# STM32_microcontroller_IOs.net
KiCad netlist of a schematic drawn in Altium Designer
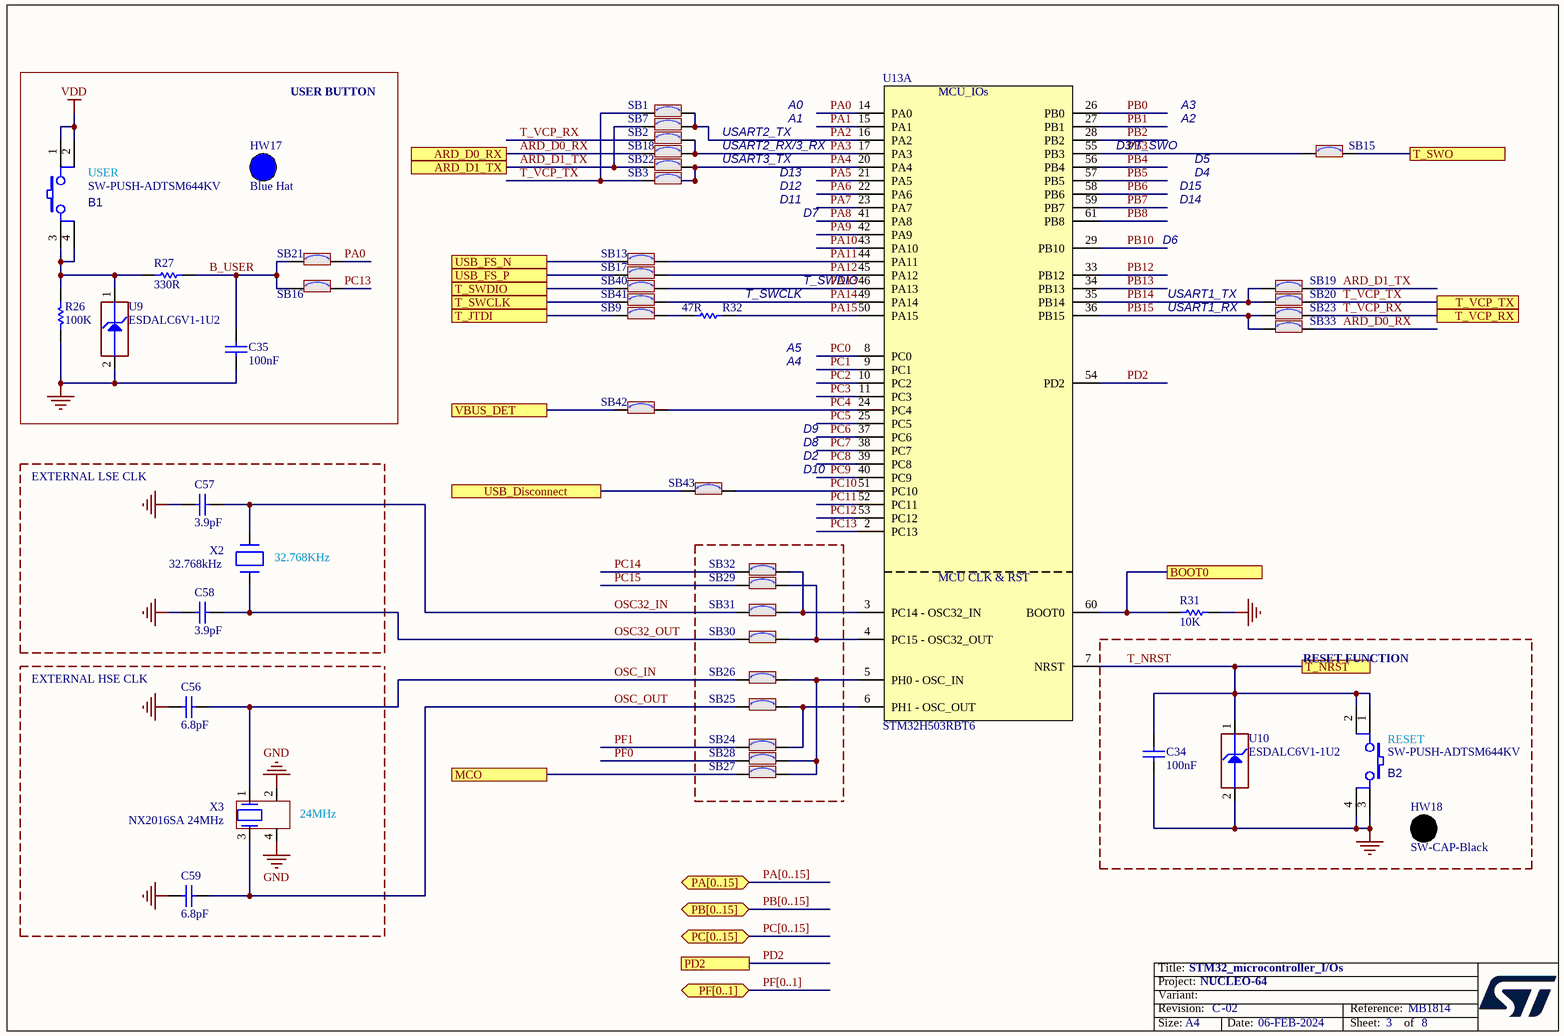
[diagram p0: STM32_microcontroller_IOs.SchDoc]

(export (version "E")
  (design (tool "Eeschema 10.0.6"))
  (components
    (comp (ref "B1")
      (value "SW-PUSH-ADTSM644KV")
      (footprint "SWI_APEM_ADTSM644KV_BLACK")
      (description "Push Button, SPST-NO, 0.05A, 12V SMT, T=7.30mm, changeable caps AKTSC62x")
      (fields (field (name "INTERNAL_PART_NUMBER") "MCD-02524") (field (name "MANUFACTURER") "APEM INC"))
      (libsource (lib "MCD_PARTS_database") (part "SW_PUSH_SMD"))
    )
    (comp (ref "B2")
      (value "SW-PUSH-ADTSM644KV")
      (footprint "SWI_APEM_ADTSM644KV_BLACK")
      (description "Push Button, SPST-NO, 0.05A, 12V SMT, T=7.30mm, changeable caps AKTSC62x")
      (fields (field (name "INTERNAL_PART_NUMBER") "MCD-02524") (field (name "MANUFACTURER") "APEM INC"))
      (libsource (lib "MCD_PARTS_database") (part "SW_PUSH_SMD"))
    )
    (comp (ref "C34")
      (value "100nF")
      (footprint "C0402")
      (description "Capacitor, MLCC, 100nF, 16V, X7R, +/-10%, 0402, T=0.5mm")
      (fields (field (name "INTERNAL_PART_NUMBER") "MCD-00006") (field (name "MANUFACTURER") "YAGEO"))
      (libsource (lib "MCD_PARTS_database") (part "Capacitor"))
    )
    (comp (ref "C35")
      (value "100nF")
      (footprint "C0402")
      (description "Capacitor, MLCC, 100nF, 16V, X7R, +/-10%, 0402, T=0.5mm")
      (fields (field (name "INTERNAL_PART_NUMBER") "MCD-00006") (field (name "MANUFACTURER") "YAGEO"))
      (libsource (lib "MCD_PARTS_database") (part "Capacitor"))
    )
    (comp (ref "C56")
      (value "6.8pF")
      (footprint "C0402")
      (description "Capacitor, MLCC, 6.8pF, 50V, NPO, +-0.25pF, 0402, T=0.5mm")
      (fields
        (field (name "INTERNAL_PART_NUMBER") "MCD-00674")
        (field (name "MANUFACTURER_PART_NUMBER") "CC0402CRNPO9BN6R8")
        (field (name "PROVIDED_BY") "SUBCO")
      )
      (libsource (lib "MCD_PARTS_database") (part "Capacitor"))
    )
    (comp (ref "C57")
      (value "3.9pF")
      (footprint "C0402")
      (description "Capacitor, MLCC, 3.9pF, 50V, NPO, +/-0.1pF, 0402, T=0.5mm")
      (fields (field (name "INTERNAL_PART_NUMBER") "MCD-01602") (field (name "MANUFACTURER") "YAGEO"))
      (libsource (lib "MCD_PARTS_database") (part "Capacitor"))
    )
    (comp (ref "C58")
      (value "3.9pF")
      (footprint "C0402")
      (description "Capacitor, MLCC, 3.9pF, 50V, NPO, +/-0.1pF, 0402, T=0.5mm")
      (fields (field (name "INTERNAL_PART_NUMBER") "MCD-01602") (field (name "MANUFACTURER") "YAGEO"))
      (libsource (lib "MCD_PARTS_database") (part "Capacitor"))
    )
    (comp (ref "C59")
      (value "6.8pF")
      (footprint "C0402")
      (description "Capacitor, MLCC, 6.8pF, 50V, NPO, +-0.25pF, 0402, T=0.5mm")
      (fields
        (field (name "INTERNAL_PART_NUMBER") "MCD-00674")
        (field (name "MANUFACTURER_PART_NUMBER") "CC0402CRNPO9BN6R8")
        (field (name "PROVIDED_BY") "SUBCO")
      )
      (libsource (lib "MCD_PARTS_database") (part "Capacitor"))
    )
    (comp (ref "HW17")
      (value "Blue Hat")
      (description "Switch hat, blue, For KTSC-62B")
      (fields (field (name "INTERNAL_PART_NUMBER") "MCD-02136") (field (name "MANUFACTURER") "APEM INC"))
      (libsource (lib "MCD_PARTS_database") (part "BUTTON_HAT_BLUE"))
    )
    (comp (ref "HW18")
      (value "SW-CAP-Black")
      (footprint "N/A")
      (description "Black round cap for ADTSM644KV")
      (fields (field (name "INTERNAL_PART_NUMBER") "MCD-02526") (field (name "MANUFACTURER") "APEM INC"))
      (libsource (lib "MCD_PARTS_database") (part "SW-CAP-Black"))
    )
    (comp (ref "R26")
      (value "100K")
      (footprint "R0603")
      (description "Resistor,100K,0603,1%,1/10W")
      (fields
        (field (name "INTERNAL_PART_NUMBER") "MCD-00223")
        (field (name "MANUFACTURER_PART_NUMBER") "RC0603FR-07100KL")
        (field (name "PROVIDED_BY") "Subcon")
      )
      (libsource (lib "MCD_PARTS_database") (part "Resistor"))
    )
    (comp (ref "R27")
      (value "330R")
      (footprint "R0603")
      (description "Resistor,330R,0603,1%,1/10W")
      (fields
        (field (name "INTERNAL_PART_NUMBER") "MCD-00197")
        (field (name "MANUFACTURER_PART_NUMBER") "RC0603FR-07330RL")
        (field (name "PROVIDED_BY") "Subcon")
      )
      (libsource (lib "MCD_PARTS_database") (part "Resistor"))
    )
    (comp (ref "R31")
      (value "10K")
      (footprint "R0603")
      (description "Resistor,10K,0603,1%,1/10W")
      (fields
        (field (name "INTERNAL_PART_NUMBER") "MCD-00220")
        (field (name "MANUFACTURER_PART_NUMBER") "RC0603FR-0710KL")
        (field (name "PROVIDED_BY") "Subcon")
      )
      (libsource (lib "MCD_PARTS_database") (part "Resistor"))
    )
    (comp (ref "R32")
      (value "47R")
      (footprint "R0402")
      (description "Resistor,47R,0402,1%,1/16W")
      (fields
        (field (name "INTERNAL_PART_NUMBER") "MCD-00481")
        (field (name "MANUFACTURER_PART_NUMBER") "RC0402FR-0747RL")
        (field (name "PROVIDED_BY") "SUBCO")
      )
      (libsource (lib "MCD_PARTS_database") (part "Resistor"))
    )
    (comp (ref "SB1")
      (value "~")
      (footprint "SOLDER-BRIDGE_R0603-0R")
      (description "Solder Bridge ON")
      (fields
        (field (name "INTERNAL_PART_NUMBER") "MCD-00071")
        (field (name "MANUFACTURER_PART_NUMBER") "RC0603JR-070RL")
        (field (name "PROVIDED_BY") "SUBCO")
      )
      (libsource (lib "") (part "SB_ON_1"))
    )
    (comp (ref "SB2")
      (value "~")
      (footprint "SOLDER-BRIDGE_R0603-0R")
      (description "Solder Bridge ON")
      (fields
        (field (name "INTERNAL_PART_NUMBER") "MCD-00071")
        (field (name "MANUFACTURER_PART_NUMBER") "RC0603JR-070RL")
        (field (name "PROVIDED_BY") "SUBCO")
      )
      (libsource (lib "") (part "SB_ON_1"))
    )
    (comp (ref "SB3")
      (value "~")
      (footprint "SOLDER-BRIDGE_R0603-0R")
      (description "Solder Bridge ON")
      (fields
        (field (name "INTERNAL_PART_NUMBER") "MCD-00071")
        (field (name "MANUFACTURER_PART_NUMBER") "RC0603JR-070RL")
        (field (name "PROVIDED_BY") "SUBCO")
      )
      (libsource (lib "") (part "SB_ON_1"))
    )
    (comp (ref "SB7")
      (value "~")
      (footprint "SOLDER-BRIDGE_R0603-0R")
      (description "Solder Bridge ON")
      (fields
        (field (name "INTERNAL_PART_NUMBER") "MCD-00071")
        (field (name "MANUFACTURER_PART_NUMBER") "RC0603JR-070RL")
        (field (name "PROVIDED_BY") "SUBCO")
      )
      (libsource (lib "") (part "SB_ON_1"))
    )
    (comp (ref "SB9")
      (value "~")
      (footprint "SOLDER-BRIDGE_R0603-0R")
      (description "Solder Bridge ON")
      (fields
        (field (name "INTERNAL_PART_NUMBER") "MCD-00071")
        (field (name "MANUFACTURER_PART_NUMBER") "RC0603JR-070RL")
        (field (name "PROVIDED_BY") "SUBCO")
      )
      (libsource (lib "MCD_PARTS_database") (part "SB_ON"))
    )
    (comp (ref "SB13")
      (value "~")
      (footprint "SOLDER-BRIDGE_R0603-0R")
      (description "Solder Bridge ON")
      (fields
        (field (name "INTERNAL_PART_NUMBER") "MCD-00071")
        (field (name "MANUFACTURER_PART_NUMBER") "RC0603JR-070RL")
        (field (name "PROVIDED_BY") "SUBCO")
      )
      (libsource (lib "MCD_PARTS_database") (part "SB_ON"))
    )
    (comp (ref "SB15")
      (value "~")
      (footprint "SOLDER-BRIDGE_R0603-0R")
      (description "Solder Bridge ON")
      (fields
        (field (name "INTERNAL_PART_NUMBER") "MCD-00071")
        (field (name "MANUFACTURER_PART_NUMBER") "RC0603JR-070RL")
        (field (name "PROVIDED_BY") "SUBCO")
      )
      (libsource (lib "MCD_PARTS_database") (part "SB_ON"))
    )
    (comp (ref "SB16")
      (value "~")
      (footprint "SOLDER-BRIDGE_R0603-0R")
      (description "Solder Bridge ON")
      (fields
        (field (name "INTERNAL_PART_NUMBER") "MCD-00071")
        (field (name "MANUFACTURER_PART_NUMBER") "RC0603JR-070RL")
        (field (name "PROVIDED_BY") "SUBCO")
      )
      (libsource (lib "MCD_PARTS_database") (part "SB_ON"))
    )
    (comp (ref "SB17")
      (value "~")
      (footprint "SOLDER-BRIDGE_R0603-0R")
      (description "Solder Bridge ON")
      (fields
        (field (name "INTERNAL_PART_NUMBER") "MCD-00071")
        (field (name "MANUFACTURER_PART_NUMBER") "RC0603JR-070RL")
        (field (name "PROVIDED_BY") "SUBCO")
      )
      (libsource (lib "MCD_PARTS_database") (part "SB_ON"))
    )
    (comp (ref "SB18")
      (value "~")
      (footprint "SOLDER-BRIDGE_R0603-0R")
      (description "Solder Bridge ON")
      (fields
        (field (name "INTERNAL_PART_NUMBER") "MCD-00071")
        (field (name "MANUFACTURER_PART_NUMBER") "RC0603JR-070RL")
        (field (name "PROVIDED_BY") "SUBCO")
      )
      (libsource (lib "") (part "SB_ON_1"))
    )
    (comp (ref "SB19")
      (value "~")
      (footprint "SOLDER-BRIDGE_R0603-0R")
      (description "Solder Bridge ON")
      (fields
        (field (name "INTERNAL_PART_NUMBER") "MCD-00071")
        (field (name "MANUFACTURER_PART_NUMBER") "RC0603JR-070RL")
        (field (name "PROVIDED_BY") "SUBCO")
      )
      (libsource (lib "") (part "SB_ON_1"))
    )
    (comp (ref "SB20")
      (value "~")
      (footprint "SOLDER-BRIDGE_R0603-0R")
      (description "Solder Bridge ON")
      (fields
        (field (name "INTERNAL_PART_NUMBER") "MCD-00071")
        (field (name "MANUFACTURER_PART_NUMBER") "RC0603JR-070RL")
        (field (name "PROVIDED_BY") "SUBCO")
      )
      (libsource (lib "") (part "SB_ON_1"))
    )
    (comp (ref "SB21")
      (value "~")
      (footprint "SOLDER-BRIDGE_R0603-0R")
      (description "Solder Bridge ON")
      (fields
        (field (name "INTERNAL_PART_NUMBER") "MCD-00071")
        (field (name "MANUFACTURER_PART_NUMBER") "RC0603JR-070RL")
        (field (name "PROVIDED_BY") "SUBCO")
      )
      (libsource (lib "MCD_PARTS_database") (part "SB_ON"))
    )
    (comp (ref "SB22")
      (value "~")
      (footprint "SOLDER-BRIDGE_R0603-0R")
      (description "Solder Bridge ON")
      (fields
        (field (name "INTERNAL_PART_NUMBER") "MCD-00071")
        (field (name "MANUFACTURER_PART_NUMBER") "RC0603JR-070RL")
        (field (name "PROVIDED_BY") "SUBCO")
      )
      (libsource (lib "") (part "SB_ON_1"))
    )
    (comp (ref "SB23")
      (value "~")
      (footprint "SOLDER-BRIDGE_R0603-0R")
      (description "Solder Bridge ON")
      (fields
        (field (name "INTERNAL_PART_NUMBER") "MCD-00071")
        (field (name "MANUFACTURER_PART_NUMBER") "RC0603JR-070RL")
        (field (name "PROVIDED_BY") "SUBCO")
      )
      (libsource (lib "") (part "SB_ON_1"))
    )
    (comp (ref "SB24")
      (value "~")
      (footprint "SOLDER-BRIDGE_R0603-0R")
      (description "Solder Bridge ON")
      (fields
        (field (name "INTERNAL_PART_NUMBER") "MCD-00071")
        (field (name "MANUFACTURER_PART_NUMBER") "RC0603JR-070RL")
        (field (name "PROVIDED_BY") "SUBCO")
      )
      (libsource (lib "MCD_PARTS_database") (part "SB_ON"))
    )
    (comp (ref "SB25")
      (value "~")
      (footprint "SOLDER-BRIDGE_R0603-0R")
      (description "Solder Bridge ON")
      (fields
        (field (name "INTERNAL_PART_NUMBER") "MCD-00071")
        (field (name "MANUFACTURER_PART_NUMBER") "RC0603JR-070RL")
        (field (name "PROVIDED_BY") "SUBCO")
      )
      (libsource (lib "MCD_PARTS_database") (part "SB_ON"))
    )
    (comp (ref "SB26")
      (value "~")
      (footprint "SOLDER-BRIDGE_R0603-0R")
      (description "Solder Bridge ON")
      (fields
        (field (name "INTERNAL_PART_NUMBER") "MCD-00071")
        (field (name "MANUFACTURER_PART_NUMBER") "RC0603JR-070RL")
        (field (name "PROVIDED_BY") "SUBCO")
      )
      (libsource (lib "MCD_PARTS_database") (part "SB_ON"))
    )
    (comp (ref "SB27")
      (value "~")
      (footprint "SOLDER-BRIDGE_R0603-0R")
      (description "Solder Bridge ON")
      (fields
        (field (name "INTERNAL_PART_NUMBER") "MCD-00071")
        (field (name "MANUFACTURER_PART_NUMBER") "RC0603JR-070RL")
        (field (name "PROVIDED_BY") "SUBCO")
      )
      (libsource (lib "MCD_PARTS_database") (part "SB_ON"))
    )
    (comp (ref "SB28")
      (value "~")
      (footprint "SOLDER-BRIDGE_R0603-0R")
      (description "Solder Bridge ON")
      (fields
        (field (name "INTERNAL_PART_NUMBER") "MCD-00071")
        (field (name "MANUFACTURER_PART_NUMBER") "RC0603JR-070RL")
        (field (name "PROVIDED_BY") "SUBCO")
      )
      (libsource (lib "MCD_PARTS_database") (part "SB_ON"))
    )
    (comp (ref "SB29")
      (value "~")
      (footprint "SOLDER-BRIDGE_R0603-0R")
      (description "Solder Bridge ON")
      (fields
        (field (name "INTERNAL_PART_NUMBER") "MCD-00071")
        (field (name "MANUFACTURER_PART_NUMBER") "RC0603JR-070RL")
        (field (name "PROVIDED_BY") "SUBCO")
      )
      (libsource (lib "MCD_PARTS_database") (part "SB_ON"))
    )
    (comp (ref "SB30")
      (value "~")
      (footprint "SOLDER-BRIDGE_R0603-0R")
      (description "Solder Bridge ON")
      (fields
        (field (name "INTERNAL_PART_NUMBER") "MCD-00071")
        (field (name "MANUFACTURER_PART_NUMBER") "RC0603JR-070RL")
        (field (name "PROVIDED_BY") "SUBCO")
      )
      (libsource (lib "MCD_PARTS_database") (part "SB_ON"))
    )
    (comp (ref "SB31")
      (value "~")
      (footprint "SOLDER-BRIDGE_R0603-0R")
      (description "Solder Bridge ON")
      (fields
        (field (name "INTERNAL_PART_NUMBER") "MCD-00071")
        (field (name "MANUFACTURER_PART_NUMBER") "RC0603JR-070RL")
        (field (name "PROVIDED_BY") "SUBCO")
      )
      (libsource (lib "MCD_PARTS_database") (part "SB_ON"))
    )
    (comp (ref "SB32")
      (value "~")
      (footprint "SOLDER-BRIDGE_R0603-0R")
      (description "Solder Bridge ON")
      (fields
        (field (name "INTERNAL_PART_NUMBER") "MCD-00071")
        (field (name "MANUFACTURER_PART_NUMBER") "RC0603JR-070RL")
        (field (name "PROVIDED_BY") "SUBCO")
      )
      (libsource (lib "MCD_PARTS_database") (part "SB_ON"))
    )
    (comp (ref "SB33")
      (value "~")
      (footprint "SOLDER-BRIDGE_R0603-0R")
      (description "Solder Bridge ON")
      (fields
        (field (name "INTERNAL_PART_NUMBER") "MCD-00071")
        (field (name "MANUFACTURER_PART_NUMBER") "RC0603JR-070RL")
        (field (name "PROVIDED_BY") "SUBCO")
      )
      (libsource (lib "") (part "SB_ON_1"))
    )
    (comp (ref "SB40")
      (value "~")
      (footprint "SOLDER-BRIDGE_R0603-0R")
      (description "Solder Bridge ON")
      (fields
        (field (name "INTERNAL_PART_NUMBER") "MCD-00071")
        (field (name "MANUFACTURER_PART_NUMBER") "RC0603JR-070RL")
        (field (name "PROVIDED_BY") "SUBCO")
      )
      (libsource (lib "MCD_PARTS_database") (part "SB_ON"))
    )
    (comp (ref "SB41")
      (value "~")
      (footprint "SOLDER-BRIDGE_R0603-0R")
      (description "Solder Bridge ON")
      (fields
        (field (name "INTERNAL_PART_NUMBER") "MCD-00071")
        (field (name "MANUFACTURER_PART_NUMBER") "RC0603JR-070RL")
        (field (name "PROVIDED_BY") "SUBCO")
      )
      (libsource (lib "MCD_PARTS_database") (part "SB_ON"))
    )
    (comp (ref "SB42")
      (value "~")
      (footprint "SOLDER-BRIDGE_R0603-0R")
      (description "Solder Bridge ON")
      (fields
        (field (name "INTERNAL_PART_NUMBER") "MCD-00071")
        (field (name "MANUFACTURER_PART_NUMBER") "RC0603JR-070RL")
        (field (name "PROVIDED_BY") "SUBCO")
      )
      (libsource (lib "MCD_PARTS_database") (part "SB_ON"))
    )
    (comp (ref "SB43")
      (value "~")
      (footprint "SOLDER-BRIDGE_R0603-0R")
      (description "Solder Bridge ON")
      (fields
        (field (name "INTERNAL_PART_NUMBER") "MCD-00071")
        (field (name "MANUFACTURER_PART_NUMBER") "RC0603JR-070RL")
        (field (name "PROVIDED_BY") "SUBCO")
      )
      (libsource (lib "MCD_PARTS_database") (part "SB_ON"))
    )
    (comp (ref "U9")
      (value "ESDALC6V1-1U2")
      (footprint "ESD_ST0201")
      (description "ESD protection 6V1")
      (fields
        (field (name "INTERNAL_PART_NUMBER") "MCD-00170")
        (field (name "MANUFACTURER") "STMICROELECTRONICS")
        (field (name "PROVIDED_BY") "Subcon")
      )
      (libsource (lib "MCD_PARTS_database") (part "ESD-TRANSIL"))
    )
    (comp (ref "U10")
      (value "ESDALC6V1-1U2")
      (footprint "ESD_ST0201")
      (description "ESD protection 6V1")
      (fields
        (field (name "INTERNAL_PART_NUMBER") "MCD-00170")
        (field (name "MANUFACTURER") "STMICROELECTRONICS")
        (field (name "PROVIDED_BY") "Subcon")
      )
      (libsource (lib "MCD_PARTS_database") (part "ESD-TRANSIL"))
    )
    (comp (ref "U13")
      (value "STM32H503RBT6")
      (footprint "ICC_LQFP64_10X10_P050_SOCKET_YAMAICHI_IC149-064-069-B5_NM")
      (description "MCU, Arm Cortex-M33, 250MHz, 32-bit MCU, 128KB flash, 32KB SRAM")
      (fields
        (field (name "INTERNAL_PART_NUMBER") "MCD-02438")
        (field (name "MANUFACTURER") "STMICROELECTRONICS")
      )
      (libsource (lib "MCD_PARTS_database") (part "STM32H503RBH6"))
    )
    (comp (ref "X2")
      (value "32.768kHz")
      (footprint "CRY_NX1610SE_2P")
      (description "Crystal, 32.768kHz, 9pF, +/-20ppm, 70KR, 1.6x1mm")
      (fields (field (name "INTERNAL_PART_NUMBER") "MCD-02291") (field (name "MANUFACTURER") "NDK"))
      (libsource (lib "MCD_PARTS_database") (part "XTAL_2_PINS"))
    )
    (comp (ref "X3")
      (value "NX2016SA 24MHz")
      (footprint "CRY_NX2016SA_4P")
      (description "Crystal 24MHz, 6pF, +-20ppm, 80ohms max, SMD")
      (fields
        (field (name "INTERNAL_PART_NUMBER") "MCD-01036")
        (field (name "MANUFACTURER_PART_NUMBER") "NX2016SA 24MHz EXS00A-CS10820")
        (field (name "PROVIDED_BY") "SUBCO")
      )
      (libsource (lib "MCD_PARTS_database") (part "XTAL_4_PINS"))
    )
  )
  (nets
    (net (code "3") (name "/ARD_D0_RX") (class "Default")
      (node (ref "SB18") (pin "2") (pinfunction "2_2") (pintype "passive"))
      (node (ref "SB33") (pin "1") (pinfunction "1_1") (pintype "passive"))
    )
    (net (code "4") (name "/ARD_D1_TX") (class "Default")
      (node (ref "SB19") (pin "1") (pinfunction "1_1") (pintype "passive"))
      (node (ref "SB22") (pin "2") (pinfunction "2_2") (pintype "passive"))
      (node (ref "SB7") (pin "2") (pinfunction "2_2") (pintype "passive"))
    )
    (net (code "5") (name "/BOOT0") (class "Default")
      (node (ref "R31") (pin "2") (pinfunction "2_2") (pintype "passive"))
      (node (ref "U13") (pin "60") (pinfunction "BOOT0_60") (pintype "passive"))
    )
    (net (code "6") (name "/B_USER") (class "Default")
      (node (ref "C35") (pin "2") (pinfunction "2_2") (pintype "passive"))
      (node (ref "R27") (pin "2") (pinfunction "2_2") (pintype "passive"))
      (node (ref "SB16") (pin "1") (pinfunction "1_1") (pintype "passive"))
      (node (ref "SB21") (pin "1") (pinfunction "1_1") (pintype "passive"))
    )
    (net (code "7") (name "/MCO") (class "Default")
      (node (ref "SB27") (pin "1") (pinfunction "1_1") (pintype "passive"))
    )
    (net (code "8") (name "/OSC32_IN") (class "Default")
      (node (ref "C57") (pin "2") (pinfunction "2_2") (pintype "passive"))
      (node (ref "SB31") (pin "1") (pinfunction "1_1") (pintype "passive"))
      (node (ref "X2") (pin "2") (pinfunction "X2_2") (pintype "passive"))
    )
    (net (code "9") (name "/OSC32_OUT") (class "Default")
      (node (ref "C58") (pin "2") (pinfunction "2_2") (pintype "passive"))
      (node (ref "SB30") (pin "1") (pinfunction "1_1") (pintype "passive"))
      (node (ref "X2") (pin "1") (pinfunction "X1_1") (pintype "passive"))
    )
    (net (code "10") (name "/OSC_IN") (class "Default")
      (node (ref "C56") (pin "2") (pinfunction "2_2") (pintype "passive"))
      (node (ref "SB26") (pin "1") (pinfunction "1_1") (pintype "passive"))
      (node (ref "X3") (pin "1") (pinfunction "1_1") (pintype "passive"))
    )
    (net (code "11") (name "/OSC_OUT") (class "Default")
      (node (ref "C59") (pin "2") (pinfunction "2_2") (pintype "passive"))
      (node (ref "SB25") (pin "1") (pinfunction "1_1") (pintype "passive"))
      (node (ref "X3") (pin "3") (pinfunction "3_3") (pintype "passive"))
    )
    (net (code "12") (name "/PA0") (class "Default")
      (node (ref "SB21") (pin "2") (pinfunction "2_2") (pintype "passive"))
      (node (ref "U13") (pin "14") (pinfunction "PA0_14") (pintype "passive"))
    )
    (net (code "13") (name "/PA1") (class "Default")
      (node (ref "U13") (pin "15") (pinfunction "PA1_15") (pintype "passive"))
    )
    (net (code "14") (name "/PA2") (class "Default")
      (node (ref "SB1") (pin "1") (pinfunction "1_1") (pintype "passive"))
      (node (ref "SB7") (pin "1") (pinfunction "1_1") (pintype "passive"))
      (node (ref "U13") (pin "16") (pinfunction "PA2_16") (pintype "passive"))
    )
    (net (code "15") (name "/PA3") (class "Default")
      (node (ref "SB18") (pin "1") (pinfunction "1_1") (pintype "passive"))
      (node (ref "SB2") (pin "1") (pinfunction "1_1") (pintype "passive"))
      (node (ref "U13") (pin "17") (pinfunction "PA3_17") (pintype "passive"))
    )
    (net (code "16") (name "/PA4") (class "Default")
      (node (ref "SB22") (pin "1") (pinfunction "1_1") (pintype "passive"))
      (node (ref "SB3") (pin "1") (pinfunction "1_1") (pintype "passive"))
      (node (ref "U13") (pin "20") (pinfunction "PA4_20") (pintype "passive"))
    )
    (net (code "17") (name "/PA5") (class "Default")
      (node (ref "U13") (pin "21") (pinfunction "PA5_21") (pintype "passive"))
    )
    (net (code "18") (name "/PA6") (class "Default")
      (node (ref "U13") (pin "22") (pinfunction "PA6_22") (pintype "passive"))
    )
    (net (code "19") (name "/PA7") (class "Default")
      (node (ref "U13") (pin "23") (pinfunction "PA7_23") (pintype "passive"))
    )
    (net (code "20") (name "/PA8") (class "Default")
      (node (ref "U13") (pin "41") (pinfunction "PA8_41") (pintype "passive"))
    )
    (net (code "21") (name "/PA9") (class "Default")
      (node (ref "U13") (pin "42") (pinfunction "PA9_42") (pintype "passive"))
    )
    (net (code "22") (name "/PA10") (class "Default")
      (node (ref "U13") (pin "43") (pinfunction "PA10_43") (pintype "passive"))
    )
    (net (code "23") (name "/PA11") (class "Default")
      (node (ref "SB13") (pin "2") (pinfunction "2_2") (pintype "passive"))
      (node (ref "U13") (pin "44") (pinfunction "PA11_44") (pintype "passive"))
    )
    (net (code "24") (name "/PA12") (class "Default")
      (node (ref "SB17") (pin "2") (pinfunction "2_2") (pintype "passive"))
      (node (ref "U13") (pin "45") (pinfunction "PA12_45") (pintype "passive"))
    )
    (net (code "25") (name "/PA13") (class "Default")
      (node (ref "SB40") (pin "2") (pinfunction "2_2") (pintype "passive"))
      (node (ref "U13") (pin "46") (pinfunction "PA13_46") (pintype "passive"))
    )
    (net (code "26") (name "/PA14") (class "Default")
      (node (ref "SB41") (pin "2") (pinfunction "2_2") (pintype "passive"))
      (node (ref "U13") (pin "49") (pinfunction "PA14_49") (pintype "passive"))
    )
    (net (code "27") (name "/PA15") (class "Default")
      (node (ref "R32") (pin "2") (pinfunction "2_2") (pintype "passive"))
      (node (ref "U13") (pin "50") (pinfunction "PA15_50") (pintype "passive"))
    )
    (net (code "29") (name "/PB0") (class "Default")
      (node (ref "U13") (pin "26") (pinfunction "PB0_26") (pintype "passive"))
    )
    (net (code "30") (name "/PB1") (class "Default")
      (node (ref "U13") (pin "27") (pinfunction "PB1_27") (pintype "passive"))
    )
    (net (code "31") (name "/PB2") (class "Default")
      (node (ref "U13") (pin "28") (pinfunction "PB2_28") (pintype "passive"))
    )
    (net (code "32") (name "/PB3") (class "Default")
      (node (ref "SB15") (pin "1") (pinfunction "1_1") (pintype "passive"))
      (node (ref "U13") (pin "55") (pinfunction "PB3_55") (pintype "passive"))
    )
    (net (code "33") (name "/PB4") (class "Default")
      (node (ref "U13") (pin "56") (pinfunction "PB4_56") (pintype "passive"))
    )
    (net (code "34") (name "/PB5") (class "Default")
      (node (ref "U13") (pin "57") (pinfunction "PB5_57") (pintype "passive"))
    )
    (net (code "35") (name "/PB6") (class "Default")
      (node (ref "U13") (pin "58") (pinfunction "PB6_58") (pintype "passive"))
    )
    (net (code "36") (name "/PB7") (class "Default")
      (node (ref "U13") (pin "59") (pinfunction "PB7_59") (pintype "passive"))
    )
    (net (code "37") (name "/PB8") (class "Default")
      (node (ref "U13") (pin "61") (pinfunction "PB8_61") (pintype "passive"))
    )
    (net (code "38") (name "/PB10") (class "Default")
      (node (ref "U13") (pin "29") (pinfunction "PB10_29") (pintype "passive"))
    )
    (net (code "39") (name "/PB12") (class "Default")
      (node (ref "U13") (pin "33") (pinfunction "PB12_33") (pintype "passive"))
    )
    (net (code "40") (name "/PB13") (class "Default")
      (node (ref "U13") (pin "34") (pinfunction "PB13_34") (pintype "passive"))
    )
    (net (code "41") (name "/PB14") (class "Default")
      (node (ref "SB19") (pin "2") (pinfunction "2_2") (pintype "passive"))
      (node (ref "SB20") (pin "2") (pinfunction "2_2") (pintype "passive"))
      (node (ref "U13") (pin "35") (pinfunction "PB14_35") (pintype "passive"))
    )
    (net (code "42") (name "/PB15") (class "Default")
      (node (ref "SB23") (pin "2") (pinfunction "2_2") (pintype "passive"))
      (node (ref "SB33") (pin "2") (pinfunction "2_2") (pintype "passive"))
      (node (ref "U13") (pin "36") (pinfunction "PB15_36") (pintype "passive"))
    )
    (net (code "44") (name "/PC0") (class "Default")
      (node (ref "U13") (pin "8") (pinfunction "PC0_8") (pintype "passive"))
    )
    (net (code "45") (name "/PC1") (class "Default")
      (node (ref "U13") (pin "9") (pinfunction "PC1_9") (pintype "passive"))
    )
    (net (code "46") (name "/PC2") (class "Default")
      (node (ref "U13") (pin "10") (pinfunction "PC2_10") (pintype "passive"))
    )
    (net (code "47") (name "/PC3") (class "Default")
      (node (ref "U13") (pin "11") (pinfunction "PC3_11") (pintype "passive"))
    )
    (net (code "48") (name "/PC4") (class "Default")
      (node (ref "SB42") (pin "2") (pinfunction "2_2") (pintype "passive"))
      (node (ref "U13") (pin "24") (pinfunction "PC4_24") (pintype "passive"))
    )
    (net (code "49") (name "/PC5") (class "Default")
      (node (ref "U13") (pin "25") (pinfunction "PC5_25") (pintype "passive"))
    )
    (net (code "50") (name "/PC6") (class "Default")
      (node (ref "U13") (pin "37") (pinfunction "PC6_37") (pintype "passive"))
    )
    (net (code "51") (name "/PC7") (class "Default")
      (node (ref "U13") (pin "38") (pinfunction "PC7_38") (pintype "passive"))
    )
    (net (code "52") (name "/PC8") (class "Default")
      (node (ref "U13") (pin "39") (pinfunction "PC8_39") (pintype "passive"))
    )
    (net (code "53") (name "/PC9") (class "Default")
      (node (ref "U13") (pin "40") (pinfunction "PC9_40") (pintype "passive"))
    )
    (net (code "54") (name "/PC10") (class "Default")
      (node (ref "SB43") (pin "2") (pinfunction "2_2") (pintype "passive"))
      (node (ref "U13") (pin "51") (pinfunction "PC10_51") (pintype "passive"))
    )
    (net (code "55") (name "/PC11") (class "Default")
      (node (ref "U13") (pin "52") (pinfunction "PC11_52") (pintype "passive"))
    )
    (net (code "56") (name "/PC12") (class "Default")
      (node (ref "U13") (pin "53") (pinfunction "PC12_53") (pintype "passive"))
    )
    (net (code "57") (name "/PC13") (class "Default")
      (node (ref "SB16") (pin "2") (pinfunction "2_2") (pintype "passive"))
      (node (ref "U13") (pin "2") (pinfunction "PC13_2") (pintype "passive"))
    )
    (net (code "58") (name "/PC14") (class "Default")
      (node (ref "SB32") (pin "1") (pinfunction "1_1") (pintype "passive"))
    )
    (net (code "59") (name "/PC15") (class "Default")
      (node (ref "SB29") (pin "1") (pinfunction "1_1") (pintype "passive"))
    )
    (net (code "61") (name "/PD2") (class "Default")
      (node (ref "U13") (pin "54") (pinfunction "PD2_54") (pintype "passive"))
    )
    (net (code "62") (name "/PF0") (class "Default")
      (node (ref "SB28") (pin "1") (pinfunction "1_1") (pintype "passive"))
    )
    (net (code "63") (name "/PF1") (class "Default")
      (node (ref "SB24") (pin "1") (pinfunction "1_1") (pintype "passive"))
    )
    (net (code "65") (name "/T_JTDI") (class "Default")
      (node (ref "SB9") (pin "1") (pinfunction "1_1") (pintype "passive"))
    )
    (net (code "66") (name "/T_NRST") (class "Default")
      (node (ref "B2") (pin "1") (pinfunction "1_1") (pintype "passive"))
      (node (ref "B2") (pin "2") (pinfunction "2_2") (pintype "passive"))
      (node (ref "C34") (pin "2") (pinfunction "2_2") (pintype "passive"))
      (node (ref "U10") (pin "1") (pinfunction "IO1_1") (pintype "passive"))
      (node (ref "U13") (pin "7") (pinfunction "NRST_7") (pintype "passive"))
    )
    (net (code "67") (name "/T_SWCLK") (class "Default")
      (node (ref "SB41") (pin "1") (pinfunction "1_1") (pintype "passive"))
    )
    (net (code "68") (name "/T_SWDIO") (class "Default")
      (node (ref "SB40") (pin "1") (pinfunction "1_1") (pintype "passive"))
    )
    (net (code "69") (name "/T_SWO") (class "Default")
      (node (ref "SB15") (pin "2") (pinfunction "2_2") (pintype "passive"))
    )
    (net (code "70") (name "/T_VCP_RX") (class "Default")
      (node (ref "SB2") (pin "2") (pinfunction "2_2") (pintype "passive"))
      (node (ref "SB23") (pin "1") (pinfunction "1_1") (pintype "passive"))
    )
    (net (code "71") (name "/T_VCP_TX") (class "Default")
      (node (ref "SB1") (pin "2") (pinfunction "2_2") (pintype "passive"))
      (node (ref "SB20") (pin "1") (pinfunction "1_1") (pintype "passive"))
      (node (ref "SB3") (pin "2") (pinfunction "2_2") (pintype "passive"))
    )
    (net (code "72") (name "/USB_Disconnect") (class "Default")
      (node (ref "SB43") (pin "1") (pinfunction "1_1") (pintype "passive"))
    )
    (net (code "73") (name "/USB_FS_N") (class "Default")
      (node (ref "SB13") (pin "1") (pinfunction "1_1") (pintype "passive"))
    )
    (net (code "74") (name "/USB_FS_P") (class "Default")
      (node (ref "SB17") (pin "1") (pinfunction "1_1") (pintype "passive"))
    )
    (net (code "75") (name "/VBUS_DET") (class "Default")
      (node (ref "SB42") (pin "1") (pinfunction "1_1") (pintype "passive"))
    )
    (net (code "76") (name "GND") (class "Default")
      (node (ref "B2") (pin "3") (pinfunction "3_3") (pintype "passive"))
      (node (ref "B2") (pin "4") (pinfunction "4_4") (pintype "passive"))
      (node (ref "C34") (pin "1") (pinfunction "1_1") (pintype "passive"))
      (node (ref "C35") (pin "1") (pinfunction "1_1") (pintype "passive"))
      (node (ref "C56") (pin "1") (pinfunction "1_1") (pintype "passive"))
      (node (ref "C57") (pin "1") (pinfunction "1_1") (pintype "passive"))
      (node (ref "C58") (pin "1") (pinfunction "1_1") (pintype "passive"))
      (node (ref "C59") (pin "1") (pinfunction "1_1") (pintype "passive"))
      (node (ref "R26") (pin "1") (pinfunction "1_1") (pintype "passive"))
      (node (ref "R31") (pin "1") (pinfunction "1_1") (pintype "passive"))
      (node (ref "U10") (pin "2") (pinfunction "GND_2") (pintype "passive"))
      (node (ref "U9") (pin "2") (pinfunction "GND_2") (pintype "passive"))
      (node (ref "X3") (pin "2") (pinfunction "2_2") (pintype "passive"))
      (node (ref "X3") (pin "4") (pinfunction "4_4") (pintype "passive"))
    )
    (net (code "77") (name "Net-(R32-Pad1)") (class "Default")
      (node (ref "R32") (pin "1") (pinfunction "1_1") (pintype "passive"))
      (node (ref "SB9") (pin "2") (pinfunction "2_2") (pintype "passive"))
    )
    (net (code "78") (name "Net-(U9-IO1)") (class "Default")
      (node (ref "B1") (pin "3") (pinfunction "3_3") (pintype "passive"))
      (node (ref "B1") (pin "4") (pinfunction "4_4") (pintype "passive"))
      (node (ref "R26") (pin "2") (pinfunction "2_2") (pintype "passive"))
      (node (ref "R27") (pin "1") (pinfunction "1_1") (pintype "passive"))
      (node (ref "U9") (pin "1") (pinfunction "IO1_1") (pintype "passive"))
    )
    (net (code "79") (name "Net-(U13A-PC14_-_OSC32_IN)") (class "Default")
      (node (ref "SB31") (pin "2") (pinfunction "2_2") (pintype "passive"))
      (node (ref "SB32") (pin "2") (pinfunction "2_2") (pintype "passive"))
      (node (ref "U13") (pin "3") (pinfunction "PC14_-_OSC32_IN_3") (pintype "passive"))
    )
    (net (code "80") (name "Net-(U13A-PC15_-_OSC32_OUT)") (class "Default")
      (node (ref "SB29") (pin "2") (pinfunction "2_2") (pintype "passive"))
      (node (ref "SB30") (pin "2") (pinfunction "2_2") (pintype "passive"))
      (node (ref "U13") (pin "4") (pinfunction "PC15_-_OSC32_OUT_4") (pintype "passive"))
    )
    (net (code "81") (name "Net-(U13A-PH0_-_OSC_IN)") (class "Default")
      (node (ref "SB26") (pin "2") (pinfunction "2_2") (pintype "passive"))
      (node (ref "SB27") (pin "2") (pinfunction "2_2") (pintype "passive"))
      (node (ref "SB28") (pin "2") (pinfunction "2_2") (pintype "passive"))
      (node (ref "U13") (pin "5") (pinfunction "PH0_-_OSC_IN_5") (pintype "passive"))
    )
    (net (code "82") (name "Net-(U13A-PH1_-_OSC_OUT)") (class "Default")
      (node (ref "SB24") (pin "2") (pinfunction "2_2") (pintype "passive"))
      (node (ref "SB25") (pin "2") (pinfunction "2_2") (pintype "passive"))
      (node (ref "U13") (pin "6") (pinfunction "PH1_-_OSC_OUT_6") (pintype "passive"))
    )
    (net (code "83") (name "VDD") (class "Default")
      (node (ref "B1") (pin "1") (pinfunction "1_1") (pintype "passive"))
      (node (ref "B1") (pin "2") (pinfunction "2_2") (pintype "passive"))
    )
  )
)
